# power.net
KiCad netlist of a schematic drawn in Altium Designer
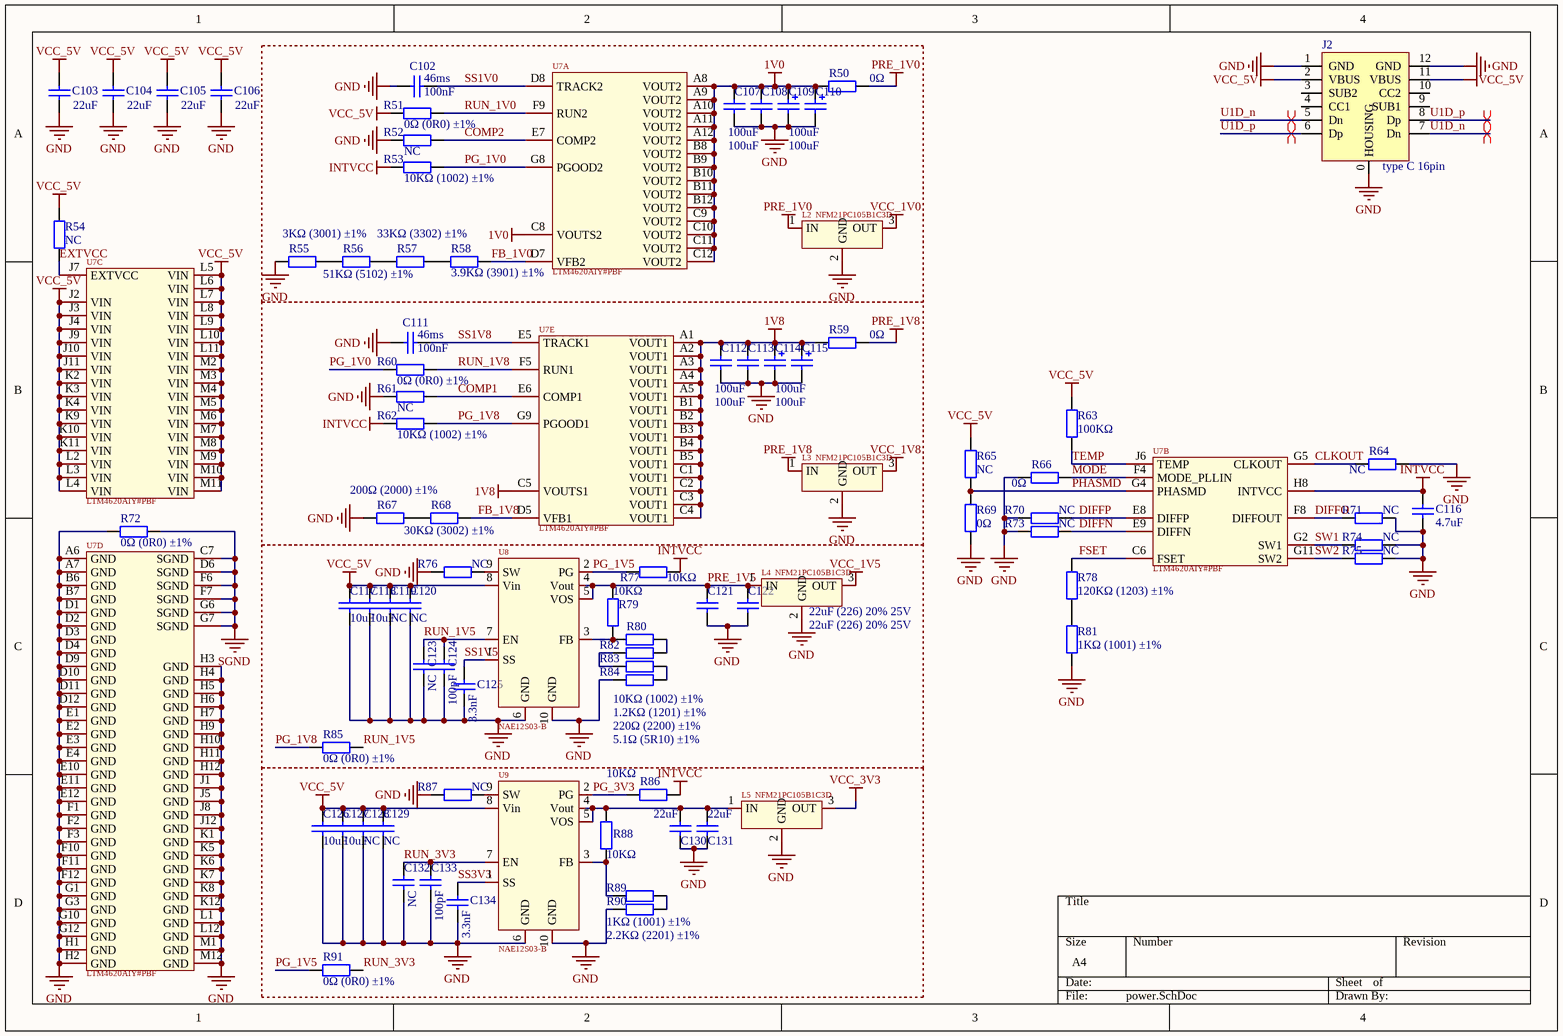
[diagram p0: power.SchDoc]

(export (version "E")
  (design (tool "Eeschema 10.0.6"))
  (components
    (comp (ref "C102")
      (value "100nF")
      (footprint "0805_C")
      (description "贴片电容")
      (libsource (lib "Miscellaneous Devices LC") (part "0805 100nF(104) 10% 50V"))
    )
    (comp (ref "C103")
      (value "22uF")
      (footprint "0805_C")
      (description "贴片电容")
      (libsource (lib "Miscellaneous Devices LC") (part "0805 22uF (226) 20% 25V"))
    )
    (comp (ref "C104")
      (value "22uF")
      (footprint "0805_C")
      (description "贴片电容")
      (libsource (lib "Miscellaneous Devices LC") (part "0805 22uF (226) 20% 25V"))
    )
    (comp (ref "C105")
      (value "22uF")
      (footprint "0805_C")
      (description "贴片电容")
      (libsource (lib "Miscellaneous Devices LC") (part "0805 22uF (226) 20% 25V"))
    )
    (comp (ref "C106")
      (value "22uF")
      (footprint "0805_C")
      (description "贴片电容")
      (libsource (lib "Miscellaneous Devices LC") (part "0805 22uF (226) 20% 25V"))
    )
    (comp (ref "C107")
      (value "100uF")
      (footprint "1206_C")
      (description "贴片电容")
      (libsource (lib "Miscellaneous Devices LC") (part "1206 100nF (104) 10% 50V"))
    )
    (comp (ref "C108")
      (value "100uF")
      (footprint "1206_C")
      (description "贴片电容")
      (libsource (lib "Miscellaneous Devices LC") (part "1206 100nF (104) 10% 50V"))
    )
    (comp (ref "C109")
      (value "100uF")
      (footprint "CASE-B_3528")
      (description "钽电容")
      (libsource (lib "Miscellaneous Devices LC") (part "3528 100uF (107) 10% 6.3V"))
    )
    (comp (ref "C110")
      (value "100uF")
      (footprint "CASE-B_3528")
      (description "钽电容")
      (libsource (lib "Miscellaneous Devices LC") (part "3528 100uF (107) 10% 6.3V"))
    )
    (comp (ref "C111")
      (value "100nF")
      (footprint "0805_C")
      (description "贴片电容")
      (libsource (lib "Miscellaneous Devices LC") (part "0805 100nF(104) 10% 50V"))
    )
    (comp (ref "C112")
      (value "100uF")
      (footprint "1206_C")
      (description "贴片电容")
      (libsource (lib "Miscellaneous Devices LC") (part "1206 100nF (104) 10% 50V"))
    )
    (comp (ref "C113")
      (value "100uF")
      (footprint "1206_C")
      (description "贴片电容")
      (libsource (lib "Miscellaneous Devices LC") (part "1206 100nF (104) 10% 50V"))
    )
    (comp (ref "C114")
      (value "100uF")
      (footprint "CASE-B_3528")
      (description "钽电容")
      (libsource (lib "Miscellaneous Devices LC") (part "3528 100uF (107) 10% 6.3V"))
    )
    (comp (ref "C115")
      (value "100uF")
      (footprint "CASE-B_3528")
      (description "钽电容")
      (libsource (lib "Miscellaneous Devices LC") (part "3528 100uF (107) 10% 6.3V"))
    )
    (comp (ref "C116")
      (value "4.7uF")
      (footprint "0805_C")
      (description "贴片电容")
      (libsource (lib "Miscellaneous Devices LC") (part "0805 4.7uF (475) 10% 25V"))
    )
    (comp (ref "C117")
      (value "10uF")
      (footprint "0805_C")
      (description "贴片电容")
      (libsource (lib "Miscellaneous Devices LC") (part "0805 10uF (106) 10% 25V"))
    )
    (comp (ref "C118")
      (value "10uF")
      (footprint "0805_C")
      (description "贴片电容")
      (libsource (lib "Miscellaneous Devices LC") (part "0805 10uF (106) 10% 25V"))
    )
    (comp (ref "C119")
      (value "NC")
      (footprint "0805_C")
      (description "贴片电容")
      (libsource (lib "Miscellaneous Devices LC") (part "0805 10uF (106) 10% 25V"))
    )
    (comp (ref "C120")
      (value "NC")
      (footprint "0805_C")
      (description "贴片电容")
      (libsource (lib "Miscellaneous Devices LC") (part "0805 10uF (106) 10% 25V"))
    )
    (comp (ref "C121")
      (value "22uF (226) 20% 25V")
      (footprint "0805_C")
      (description "贴片电容")
      (libsource (lib "Miscellaneous Devices LC") (part "0805 22uF (226) 20% 25V"))
    )
    (comp (ref "C122")
      (value "22uF (226) 20% 25V")
      (footprint "0805_C")
      (description "贴片电容")
      (libsource (lib "Miscellaneous Devices LC") (part "0805 22uF (226) 20% 25V"))
    )
    (comp (ref "C123")
      (value "NC")
      (footprint "0805_C")
      (description "贴片电容")
      (libsource (lib "Miscellaneous Devices LC") (part "0805 100pF (101) 5% 50V"))
    )
    (comp (ref "C124")
      (value "100pF")
      (footprint "0805_C")
      (description "贴片电容")
      (libsource (lib "Miscellaneous Devices LC") (part "0805 100pF (101) 5% 50V"))
    )
    (comp (ref "C125")
      (value "3.3nF")
      (footprint "0805_C")
      (description "贴片电容")
      (libsource (lib "Miscellaneous Devices LC") (part "0805 3.3nF (332) 10% 50V"))
    )
    (comp (ref "C126")
      (value "10uF")
      (footprint "0805_C")
      (description "贴片电容")
      (libsource (lib "Miscellaneous Devices LC") (part "0805 10uF (106) 10% 25V"))
    )
    (comp (ref "C127")
      (value "10uF")
      (footprint "0805_C")
      (description "贴片电容")
      (libsource (lib "Miscellaneous Devices LC") (part "0805 10uF (106) 10% 25V"))
    )
    (comp (ref "C128")
      (value "NC")
      (footprint "0805_C")
      (description "贴片电容")
      (libsource (lib "Miscellaneous Devices LC") (part "0805 10uF (106) 10% 25V"))
    )
    (comp (ref "C129")
      (value "NC")
      (footprint "0805_C")
      (description "贴片电容")
      (libsource (lib "Miscellaneous Devices LC") (part "0805 10uF (106) 10% 25V"))
    )
    (comp (ref "C130")
      (value "22uF")
      (footprint "0805_C")
      (description "贴片电容")
      (libsource (lib "Miscellaneous Devices LC") (part "0805 22uF (226) 20% 25V"))
    )
    (comp (ref "C131")
      (value "22uF")
      (footprint "0805_C")
      (description "贴片电容")
      (libsource (lib "Miscellaneous Devices LC") (part "0805 22uF (226) 20% 25V"))
    )
    (comp (ref "C132")
      (value "NC")
      (footprint "0805_C")
      (description "贴片电容")
      (libsource (lib "Miscellaneous Devices LC") (part "0805 100pF (101) 5% 50V"))
    )
    (comp (ref "C133")
      (value "100pF")
      (footprint "0805_C")
      (description "贴片电容")
      (libsource (lib "Miscellaneous Devices LC") (part "0805 100pF (101) 5% 50V"))
    )
    (comp (ref "C134")
      (value "3.3nF")
      (footprint "0805_C")
      (description "贴片电容")
      (libsource (lib "Miscellaneous Devices LC") (part "0805 3.3nF (332) 10% 50V"))
    )
    (comp (ref "J2")
      (value "type C 16pin")
      (footprint "USB type C  16pin")
      (description "16针脚C口")
      (libsource (lib "五向开关") (part "USB type C 16pin"))
    )
    (comp (ref "L2")
      (value "NFM21PC105B1C3D")
      (footprint "FILTER-SMD_3P-L2.0-W1.2-L")
      (description "穿心电容")
      (fields (field (name "MANUFACTURER") "muRata(村田)"))
      (libsource (lib "五向开关") (part "NFM21PC105B1C3D"))
    )
    (comp (ref "L3")
      (value "NFM21PC105B1C3D")
      (footprint "FILTER-SMD_3P-L2.0-W1.2-L")
      (description "穿心电容")
      (fields (field (name "MANUFACTURER") "muRata(村田)"))
      (libsource (lib "五向开关") (part "NFM21PC105B1C3D"))
    )
    (comp (ref "L4")
      (value "NFM21PC105B1C3D")
      (footprint "FILTER-SMD_3P-L2.0-W1.2-L")
      (description "穿心电容")
      (fields (field (name "MANUFACTURER") "muRata(村田)"))
      (libsource (lib "五向开关") (part "NFM21PC105B1C3D"))
    )
    (comp (ref "L5")
      (value "NFM21PC105B1C3D")
      (footprint "FILTER-SMD_3P-L2.0-W1.2-L")
      (description "穿心电容")
      (fields (field (name "MANUFACTURER") "muRata(村田)"))
      (libsource (lib "五向开关") (part "NFM21PC105B1C3D"))
    )
    (comp (ref "R50")
      (value "0Ω")
      (footprint "0805_R")
      (description "贴片电阻")
      (libsource (lib "") (part "0805 0Ω (0R0) 1%_1"))
    )
    (comp (ref "R51")
      (value "0Ω (0R0) ±1%")
      (footprint "0805_R")
      (description "贴片电阻")
      (libsource (lib "Miscellaneous Devices LC") (part "0805 0Ω (0R0) 1%"))
    )
    (comp (ref "R52")
      (value "NC")
      (footprint "0805_R")
      (description "贴片电阻")
      (libsource (lib "Miscellaneous Devices LC") (part "0805 33KΩ (3302) 1%"))
    )
    (comp (ref "R53")
      (value "10KΩ (1002) ±1%")
      (footprint "0805_R")
      (description "贴片电阻")
      (libsource (lib "Miscellaneous Devices LC") (part "0805 10KΩ (1002) 1%"))
    )
    (comp (ref "R54")
      (value "NC")
      (footprint "0805_R")
      (description "贴片电阻")
      (libsource (lib "Miscellaneous Devices LC") (part "0805 3KΩ (3001) 1%"))
    )
    (comp (ref "R55")
      (value "3KΩ (3001) ±1%")
      (footprint "0805_R")
      (description "贴片电阻")
      (libsource (lib "") (part "0805 3KΩ (3001) 1%_1"))
    )
    (comp (ref "R56")
      (value "51KΩ (5102) ±1%")
      (footprint "0805_R")
      (description "贴片电阻")
      (libsource (lib "Miscellaneous Devices LC") (part "0805 51KΩ (5102) 1%"))
    )
    (comp (ref "R57")
      (value "33KΩ (3302) ±1%")
      (footprint "0805_R")
      (description "贴片电阻")
      (libsource (lib "Miscellaneous Devices LC") (part "0805 33KΩ (3302) 1%"))
    )
    (comp (ref "R58")
      (value "3.9KΩ (3901) ±1%")
      (footprint "0805_R")
      (description "贴片电阻")
      (libsource (lib "Miscellaneous Devices LC") (part "0805 3.9KΩ (3901) 1%"))
    )
    (comp (ref "R59")
      (value "0Ω")
      (footprint "0805_R")
      (description "贴片电阻")
      (libsource (lib "") (part "0805 0Ω (0R0) 1%_1"))
    )
    (comp (ref "R60")
      (value "0Ω (0R0) ±1%")
      (footprint "0805_R")
      (description "贴片电阻")
      (libsource (lib "Miscellaneous Devices LC") (part "0805 0Ω (0R0) 1%"))
    )
    (comp (ref "R61")
      (value "NC")
      (footprint "0805_R")
      (description "贴片电阻")
      (libsource (lib "Miscellaneous Devices LC") (part "0805 33KΩ (3302) 1%"))
    )
    (comp (ref "R62")
      (value "10KΩ (1002) ±1%")
      (footprint "0805_R")
      (description "贴片电阻")
      (libsource (lib "Miscellaneous Devices LC") (part "0805 10KΩ (1002) 1%"))
    )
    (comp (ref "R63")
      (value "100KΩ")
      (footprint "0805_R")
      (description "贴片电阻")
      (libsource (lib "Miscellaneous Devices LC") (part "0805 100KΩ (1003) 1%"))
    )
    (comp (ref "R64")
      (value "NC")
      (footprint "0805_R")
      (description "贴片电阻")
      (libsource (lib "Miscellaneous Devices LC") (part "0805 0Ω (0R0) 1%"))
    )
    (comp (ref "R65")
      (value "NC")
      (footprint "0805_R")
      (description "贴片电阻")
      (libsource (lib "") (part "0805 0Ω (0R0) 1%_2"))
    )
    (comp (ref "R66")
      (value "0Ω")
      (footprint "0805_R")
      (description "贴片电阻")
      (libsource (lib "Miscellaneous Devices LC") (part "0805 0Ω (0R0) 1%"))
    )
    (comp (ref "R67")
      (value "200Ω (2000) ±1%")
      (footprint "0805_R")
      (description "贴片电阻")
      (libsource (lib "Miscellaneous Devices LC") (part "0805 200Ω (2000) 1%"))
    )
    (comp (ref "R68")
      (value "30KΩ (3002) ±1%")
      (footprint "0805_R")
      (description "贴片电阻")
      (libsource (lib "Miscellaneous Devices LC") (part "0805 33KΩ (3302) 1%"))
    )
    (comp (ref "R69")
      (value "0Ω")
      (footprint "0805_R")
      (description "贴片电阻")
      (libsource (lib "") (part "0805 0Ω (0R0) 1%_2"))
    )
    (comp (ref "R70")
      (value "NC")
      (footprint "0805_R")
      (description "贴片电阻")
      (libsource (lib "Miscellaneous Devices LC") (part "0805 0Ω (0R0) 1%"))
    )
    (comp (ref "R71")
      (value "NC")
      (footprint "0805_R")
      (description "贴片电阻")
      (libsource (lib "Miscellaneous Devices LC") (part "0805 0Ω (0R0) 1%"))
    )
    (comp (ref "R72")
      (value "0Ω (0R0) ±1%")
      (footprint "0402_R")
      (description "贴片电阻")
      (libsource (lib "Miscellaneous Devices LC") (part "0805 0Ω (0R0) 1%"))
    )
    (comp (ref "R73")
      (value "NC")
      (footprint "0805_R")
      (description "贴片电阻")
      (libsource (lib "Miscellaneous Devices LC") (part "0805 0Ω (0R0) 1%"))
    )
    (comp (ref "R74")
      (value "NC")
      (footprint "0805_R")
      (description "贴片电阻")
      (libsource (lib "Miscellaneous Devices LC") (part "0805 0Ω (0R0) 1%"))
    )
    (comp (ref "R75")
      (value "NC")
      (footprint "0805_R")
      (description "贴片电阻")
      (libsource (lib "Miscellaneous Devices LC") (part "0805 0Ω (0R0) 1%"))
    )
    (comp (ref "R76")
      (value "NC")
      (footprint "0805_R")
      (description "贴片电阻")
      (libsource (lib "Miscellaneous Devices LC") (part "0805 0Ω (0R0) 1%"))
    )
    (comp (ref "R77")
      (value "10KΩ")
      (footprint "0805_R")
      (description "贴片电阻")
      (libsource (lib "") (part "0805 10KΩ (1002) 1%_1"))
    )
    (comp (ref "R78")
      (value "120KΩ (1203) ±1%")
      (footprint "0805_R")
      (description "贴片电阻")
      (libsource (lib "Miscellaneous Devices LC") (part "0402 120KΩ (1203) 1%"))
    )
    (comp (ref "R79")
      (value "10KΩ")
      (footprint "0805_R")
      (description "贴片电阻")
      (libsource (lib "") (part "0805 10KΩ (1002) 1%_2"))
    )
    (comp (ref "R80")
      (value "10KΩ (1002) ±1%")
      (footprint "0805_R")
      (description "贴片电阻")
      (libsource (lib "") (part "0805 10KΩ (1002) 1%_1"))
    )
    (comp (ref "R81")
      (value "1KΩ (1001) ±1%")
      (footprint "0805_R")
      (description "贴片电阻")
      (libsource (lib "Miscellaneous Devices LC") (part "0402 1KΩ (1001) 1%"))
    )
    (comp (ref "R82")
      (value "1.2KΩ (1201) ±1%")
      (footprint "0805_R")
      (description "贴片电阻")
      (libsource (lib "Miscellaneous Devices LC") (part "0805 1.2KΩ (1201) 1%"))
    )
    (comp (ref "R83")
      (value "220Ω (2200) ±1%")
      (footprint "0805_R")
      (description "贴片电阻")
      (libsource (lib "Miscellaneous Devices LC") (part "0805 220Ω (2200) 1%"))
    )
    (comp (ref "R84")
      (value "5.1Ω (5R10) ±1%")
      (footprint "0805_R")
      (description "贴片电阻")
      (libsource (lib "Miscellaneous Devices LC") (part "0805 5.1Ω (5R10) 1%"))
    )
    (comp (ref "R85")
      (value "0Ω (0R0) ±1%")
      (footprint "0805_R")
      (description "贴片电阻")
      (libsource (lib "Miscellaneous Devices LC") (part "0805 0Ω (0R0) 1%"))
    )
    (comp (ref "R86")
      (value "10KΩ")
      (footprint "0805_R")
      (description "贴片电阻")
      (libsource (lib "") (part "0805 10KΩ (1002) 1%_1"))
    )
    (comp (ref "R87")
      (value "NC")
      (footprint "0805_R")
      (description "贴片电阻")
      (libsource (lib "Miscellaneous Devices LC") (part "0805 0Ω (0R0) 1%"))
    )
    (comp (ref "R88")
      (value "10KΩ")
      (footprint "0805_R")
      (description "贴片电阻")
      (libsource (lib "") (part "0805 10KΩ (1002) 1%_2"))
    )
    (comp (ref "R89")
      (value "2.2KΩ (2201) ±1%")
      (footprint "0805_R")
      (description "贴片电阻")
      (libsource (lib "Miscellaneous Devices LC") (part "0805 2.2KΩ (2201) 1%"))
    )
    (comp (ref "R90")
      (value "1KΩ (1001) ±1%")
      (footprint "0805_R")
      (description "贴片电阻")
      (libsource (lib "Miscellaneous Devices LC") (part "0805 1KΩ (1001) 1%"))
    )
    (comp (ref "R91")
      (value "0Ω (0R0) ±1%")
      (footprint "0805_R")
      (description "贴片电阻")
      (libsource (lib "Miscellaneous Devices LC") (part "0805 0Ω (0R0) 1%"))
    )
    (comp (ref "U7")
      (value "LTM4620AIY#PBF")
      (footprint "BGA-144_L15.0-W15.0-R12-C12-P1.27-BL")
      (description "ADI电源")
      (fields (field (name "MANUFACTURER") "ADI(亚德诺)"))
      (libsource (lib "五向开关") (part "LTM4620AIY#PBF"))
    )
    (comp (ref "U8")
      (value "NAE12S03-B")
      (footprint "PWRM-SMD_HUAWEI_NAE12S03")
      (description "华为电源模块")
      (fields (field (name "MANUFACTURER") "HUAWEI(华为)"))
      (libsource (lib "五向开关") (part "NAE12S03-B"))
    )
    (comp (ref "U9")
      (value "NAE12S03-B")
      (footprint "PWRM-SMD_HUAWEI_NAE12S03")
      (description "华为电源模块")
      (fields (field (name "MANUFACTURER") "HUAWEI(华为)"))
      (libsource (lib "五向开关") (part "NAE12S03-B"))
    )
  )
  (nets
    (net (code "1") (name "/CLKOUT") (class "Default")
      (node (ref "R64") (pin "2") (pinfunction "2_2") (pintype "passive"))
      (node (ref "U7") (pin "G5") (pinfunction "CLKOUT_G5") (pintype "passive"))
    )
    (net (code "2") (name "/COMP1") (class "Default")
      (node (ref "R61") (pin "2") (pinfunction "2_2") (pintype "passive"))
      (node (ref "U7") (pin "E6") (pinfunction "COMP1_E6") (pintype "passive"))
    )
    (net (code "3") (name "/COMP2") (class "Default")
      (node (ref "R52") (pin "2") (pinfunction "2_2") (pintype "passive"))
      (node (ref "U7") (pin "E7") (pinfunction "COMP2_E7") (pintype "passive"))
    )
    (net (code "4") (name "/DIFFN") (class "Default")
      (node (ref "R73") (pin "1") (pinfunction "1_1") (pintype "passive"))
      (node (ref "U7") (pin "E9") (pinfunction "DIFFN_E9") (pintype "passive"))
    )
    (net (code "5") (name "/DIFFO") (class "Default")
      (node (ref "R71") (pin "2") (pinfunction "2_2") (pintype "passive"))
      (node (ref "U7") (pin "F8") (pinfunction "DIFFOUT_F8") (pintype "passive"))
    )
    (net (code "6") (name "/DIFFP") (class "Default")
      (node (ref "R70") (pin "1") (pinfunction "1_1") (pintype "passive"))
      (node (ref "U7") (pin "E8") (pinfunction "DIFFP_E8") (pintype "passive"))
    )
    (net (code "7") (name "/EXTVCC") (class "Default")
      (node (ref "R54") (pin "2") (pinfunction "2_2") (pintype "passive"))
      (node (ref "U7") (pin "J7") (pinfunction "EXTVCC_J7") (pintype "passive"))
    )
    (net (code "8") (name "/FB_1V0") (class "Default")
      (node (ref "R58") (pin "2") (pinfunction "2_2") (pintype "passive"))
      (node (ref "U7") (pin "D7") (pinfunction "VFB2_D7") (pintype "passive"))
    )
    (net (code "9") (name "/FB_1V8") (class "Default")
      (node (ref "R68") (pin "2") (pinfunction "2_2") (pintype "passive"))
      (node (ref "U7") (pin "D5") (pinfunction "VFB1_D5") (pintype "passive"))
    )
    (net (code "10") (name "/FSET") (class "Default")
      (node (ref "R78") (pin "2") (pinfunction "2_2") (pintype "passive"))
      (node (ref "U7") (pin "C6") (pinfunction "FSET_C6") (pintype "passive"))
    )
    (net (code "11") (name "/MODE") (class "Default")
      (node (ref "R66") (pin "1") (pinfunction "1_1") (pintype "passive"))
      (node (ref "U7") (pin "F4") (pinfunction "MODE_PLLIN_F4") (pintype "passive"))
    )
    (net (code "12") (name "/PG_1V0") (class "Default")
      (node (ref "R53") (pin "1") (pinfunction "1_1") (pintype "passive"))
      (node (ref "R60") (pin "2") (pinfunction "2_2") (pintype "passive"))
      (node (ref "U7") (pin "G8") (pinfunction "PGOOD2_G8") (pintype "passive"))
    )
    (net (code "13") (name "/PG_1V5") (class "Default")
      (node (ref "R77") (pin "1") (pinfunction "1_1") (pintype "passive"))
      (node (ref "R91") (pin "2") (pinfunction "2_2") (pintype "passive"))
      (node (ref "U8") (pin "2") (pinfunction "PG_2") (pintype "passive"))
    )
    (net (code "14") (name "/PG_1V8") (class "Default")
      (node (ref "R62") (pin "1") (pinfunction "1_1") (pintype "passive"))
      (node (ref "R85") (pin "2") (pinfunction "2_2") (pintype "passive"))
      (node (ref "U7") (pin "G9") (pinfunction "PGOOD1_G9") (pintype "passive"))
    )
    (net (code "15") (name "/PG_3V3") (class "Default")
      (node (ref "R86") (pin "1") (pinfunction "1_1") (pintype "passive"))
      (node (ref "U9") (pin "2") (pinfunction "PG_2") (pintype "passive"))
    )
    (net (code "16") (name "/PHASMD") (class "Default")
      (node (ref "R65") (pin "1") (pinfunction "1_1") (pintype "passive"))
      (node (ref "R69") (pin "2") (pinfunction "2_2") (pintype "passive"))
      (node (ref "U7") (pin "G4") (pinfunction "PHASMD_G4") (pintype "passive"))
    )
    (net (code "17") (name "/PRE_1V5") (class "Default")
      (node (ref "C121") (pin "2") (pinfunction "2_2") (pintype "passive"))
      (node (ref "C122") (pin "2") (pinfunction "2_2") (pintype "passive"))
      (node (ref "L4") (pin "1") (pinfunction "IN_1") (pintype "passive"))
      (node (ref "R79") (pin "2") (pinfunction "2_2") (pintype "passive"))
      (node (ref "U8") (pin "4") (pinfunction "Vout_4") (pintype "passive"))
      (node (ref "U8") (pin "5") (pinfunction "VOS_5") (pintype "passive"))
    )
    (net (code "18") (name "/RUN_1V0") (class "Default")
      (node (ref "R51") (pin "1") (pinfunction "1_1") (pintype "passive"))
      (node (ref "U7") (pin "F9") (pinfunction "RUN2_F9") (pintype "passive"))
    )
    (net (code "19") (name "/RUN_1V5") (class "Default")
      (node (ref "C123") (pin "2") (pinfunction "2_2") (pintype "passive"))
      (node (ref "C124") (pin "2") (pinfunction "2_2") (pintype "passive"))
      (node (ref "R85") (pin "1") (pinfunction "1_1") (pintype "passive"))
      (node (ref "U8") (pin "7") (pinfunction "EN_7") (pintype "passive"))
    )
    (net (code "20") (name "/RUN_1V8") (class "Default")
      (node (ref "R60") (pin "1") (pinfunction "1_1") (pintype "passive"))
      (node (ref "U7") (pin "F5") (pinfunction "RUN1_F5") (pintype "passive"))
    )
    (net (code "21") (name "/RUN_3V3") (class "Default")
      (node (ref "C132") (pin "2") (pinfunction "2_2") (pintype "passive"))
      (node (ref "C133") (pin "2") (pinfunction "2_2") (pintype "passive"))
      (node (ref "R91") (pin "1") (pinfunction "1_1") (pintype "passive"))
      (node (ref "U9") (pin "7") (pinfunction "EN_7") (pintype "passive"))
    )
    (net (code "22") (name "/SS1V0") (class "Default")
      (node (ref "C102") (pin "1") (pinfunction "1_1") (pintype "passive"))
      (node (ref "U7") (pin "D8") (pinfunction "TRACK2_D8") (pintype "passive"))
    )
    (net (code "23") (name "/SS1V5") (class "Default")
      (node (ref "C125") (pin "2") (pinfunction "2_2") (pintype "passive"))
      (node (ref "U8") (pin "1") (pinfunction "SS_1") (pintype "passive"))
    )
    (net (code "24") (name "/SS1V8") (class "Default")
      (node (ref "C111") (pin "1") (pinfunction "1_1") (pintype "passive"))
      (node (ref "U7") (pin "E5") (pinfunction "TRACK1_E5") (pintype "passive"))
    )
    (net (code "25") (name "/SS3V3") (class "Default")
      (node (ref "C134") (pin "2") (pinfunction "2_2") (pintype "passive"))
      (node (ref "U9") (pin "1") (pinfunction "SS_1") (pintype "passive"))
    )
    (net (code "26") (name "/SW1") (class "Default")
      (node (ref "R74") (pin "2") (pinfunction "2_2") (pintype "passive"))
      (node (ref "U7") (pin "G2") (pinfunction "SW1_G2") (pintype "passive"))
    )
    (net (code "27") (name "/SW2") (class "Default")
      (node (ref "R75") (pin "2") (pinfunction "2_2") (pintype "passive"))
      (node (ref "U7") (pin "G11") (pinfunction "SW2_G11") (pintype "passive"))
    )
    (net (code "28") (name "/TEMP") (class "Default")
      (node (ref "R63") (pin "1") (pinfunction "1_1") (pintype "passive"))
      (node (ref "U7") (pin "J6") (pinfunction "TEMP_J6") (pintype "passive"))
    )
    (net (code "29") (name "/U1D_n") (class "Default")
      (node (ref "J2") (pin "5") (pinfunction "Dn_5") (pintype "passive"))
      (node (ref "J2") (pin "7") (pinfunction "Dn_7") (pintype "passive"))
    )
    (net (code "30") (name "/U1D_p") (class "Default")
      (node (ref "J2") (pin "6") (pinfunction "Dp_6") (pintype "passive"))
      (node (ref "J2") (pin "8") (pinfunction "Dp_8") (pintype "passive"))
    )
    (net (code "31") (name "1V0") (class "Default")
      (node (ref "C107") (pin "2") (pinfunction "2_2") (pintype "passive"))
      (node (ref "C108") (pin "2") (pinfunction "2_2") (pintype "passive"))
      (node (ref "C109") (pin "1") (pinfunction "1_1") (pintype "passive"))
      (node (ref "C110") (pin "1") (pinfunction "1_1") (pintype "passive"))
      (node (ref "R50") (pin "1") (pinfunction "1_1") (pintype "passive"))
      (node (ref "U7") (pin "A10") (pinfunction "VOUT2_A10") (pintype "passive"))
      (node (ref "U7") (pin "A11") (pinfunction "VOUT2_A11") (pintype "passive"))
      (node (ref "U7") (pin "A12") (pinfunction "VOUT2_A12") (pintype "passive"))
      (node (ref "U7") (pin "A8") (pinfunction "VOUT2_A8") (pintype "passive"))
      (node (ref "U7") (pin "A9") (pinfunction "VOUT2_A9") (pintype "passive"))
      (node (ref "U7") (pin "B10") (pinfunction "VOUT2_B10") (pintype "passive"))
      (node (ref "U7") (pin "B11") (pinfunction "VOUT2_B11") (pintype "passive"))
      (node (ref "U7") (pin "B12") (pinfunction "VOUT2_B12") (pintype "passive"))
      (node (ref "U7") (pin "B8") (pinfunction "VOUT2_B8") (pintype "passive"))
      (node (ref "U7") (pin "B9") (pinfunction "VOUT2_B9") (pintype "passive"))
      (node (ref "U7") (pin "C10") (pinfunction "VOUT2_C10") (pintype "passive"))
      (node (ref "U7") (pin "C11") (pinfunction "VOUT2_C11") (pintype "passive"))
      (node (ref "U7") (pin "C12") (pinfunction "VOUT2_C12") (pintype "passive"))
      (node (ref "U7") (pin "C8") (pinfunction "VOUTS2_C8") (pintype "passive"))
      (node (ref "U7") (pin "C9") (pinfunction "VOUT2_C9") (pintype "passive"))
    )
    (net (code "32") (name "1V8") (class "Default")
      (node (ref "C112") (pin "2") (pinfunction "2_2") (pintype "passive"))
      (node (ref "C113") (pin "2") (pinfunction "2_2") (pintype "passive"))
      (node (ref "C114") (pin "1") (pinfunction "1_1") (pintype "passive"))
      (node (ref "C115") (pin "1") (pinfunction "1_1") (pintype "passive"))
      (node (ref "R59") (pin "1") (pinfunction "1_1") (pintype "passive"))
      (node (ref "U7") (pin "A1") (pinfunction "VOUT1_A1") (pintype "passive"))
      (node (ref "U7") (pin "A2") (pinfunction "VOUT1_A2") (pintype "passive"))
      (node (ref "U7") (pin "A3") (pinfunction "VOUT1_A3") (pintype "passive"))
      (node (ref "U7") (pin "A4") (pinfunction "VOUT1_A4") (pintype "passive"))
      (node (ref "U7") (pin "A5") (pinfunction "VOUT1_A5") (pintype "passive"))
      (node (ref "U7") (pin "B1") (pinfunction "VOUT1_B1") (pintype "passive"))
      (node (ref "U7") (pin "B2") (pinfunction "VOUT1_B2") (pintype "passive"))
      (node (ref "U7") (pin "B3") (pinfunction "VOUT1_B3") (pintype "passive"))
      (node (ref "U7") (pin "B4") (pinfunction "VOUT1_B4") (pintype "passive"))
      (node (ref "U7") (pin "B5") (pinfunction "VOUT1_B5") (pintype "passive"))
      (node (ref "U7") (pin "C1") (pinfunction "VOUT1_C1") (pintype "passive"))
      (node (ref "U7") (pin "C2") (pinfunction "VOUT1_C2") (pintype "passive"))
      (node (ref "U7") (pin "C3") (pinfunction "VOUT1_C3") (pintype "passive"))
      (node (ref "U7") (pin "C4") (pinfunction "VOUT1_C4") (pintype "passive"))
      (node (ref "U7") (pin "C5") (pinfunction "VOUTS1_C5") (pintype "passive"))
    )
    (net (code "33") (name "GND") (class "Default")
      (node (ref "C102") (pin "2") (pinfunction "2_2") (pintype "passive"))
      (node (ref "C103") (pin "1") (pinfunction "1_1") (pintype "passive"))
      (node (ref "C104") (pin "1") (pinfunction "1_1") (pintype "passive"))
      (node (ref "C105") (pin "1") (pinfunction "1_1") (pintype "passive"))
      (node (ref "C106") (pin "1") (pinfunction "1_1") (pintype "passive"))
      (node (ref "C107") (pin "1") (pinfunction "1_1") (pintype "passive"))
      (node (ref "C108") (pin "1") (pinfunction "1_1") (pintype "passive"))
      (node (ref "C109") (pin "2") (pinfunction "2_2") (pintype "passive"))
      (node (ref "C110") (pin "2") (pinfunction "2_2") (pintype "passive"))
      (node (ref "C111") (pin "2") (pinfunction "2_2") (pintype "passive"))
      (node (ref "C112") (pin "1") (pinfunction "1_1") (pintype "passive"))
      (node (ref "C113") (pin "1") (pinfunction "1_1") (pintype "passive"))
      (node (ref "C114") (pin "2") (pinfunction "2_2") (pintype "passive"))
      (node (ref "C115") (pin "2") (pinfunction "2_2") (pintype "passive"))
      (node (ref "C116") (pin "1") (pinfunction "1_1") (pintype "passive"))
      (node (ref "C117") (pin "1") (pinfunction "1_1") (pintype "passive"))
      (node (ref "C118") (pin "1") (pinfunction "1_1") (pintype "passive"))
      (node (ref "C119") (pin "1") (pinfunction "1_1") (pintype "passive"))
      (node (ref "C120") (pin "1") (pinfunction "1_1") (pintype "passive"))
      (node (ref "C121") (pin "1") (pinfunction "1_1") (pintype "passive"))
      (node (ref "C122") (pin "1") (pinfunction "1_1") (pintype "passive"))
      (node (ref "C123") (pin "1") (pinfunction "1_1") (pintype "passive"))
      (node (ref "C124") (pin "1") (pinfunction "1_1") (pintype "passive"))
      (node (ref "C125") (pin "1") (pinfunction "1_1") (pintype "passive"))
      (node (ref "C126") (pin "1") (pinfunction "1_1") (pintype "passive"))
      (node (ref "C127") (pin "1") (pinfunction "1_1") (pintype "passive"))
      (node (ref "C128") (pin "1") (pinfunction "1_1") (pintype "passive"))
      (node (ref "C129") (pin "1") (pinfunction "1_1") (pintype "passive"))
      (node (ref "C130") (pin "1") (pinfunction "1_1") (pintype "passive"))
      (node (ref "C131") (pin "1") (pinfunction "1_1") (pintype "passive"))
      (node (ref "C132") (pin "1") (pinfunction "1_1") (pintype "passive"))
      (node (ref "C133") (pin "1") (pinfunction "1_1") (pintype "passive"))
      (node (ref "C134") (pin "1") (pinfunction "1_1") (pintype "passive"))
      (node (ref "J2") (pin "0") (pinfunction "HOUSING_0") (pintype "passive"))
      (node (ref "J2") (pin "1") (pinfunction "GND_1") (pintype "passive"))
      (node (ref "J2") (pin "12") (pinfunction "GND_12") (pintype "passive"))
      (node (ref "L2") (pin "2") (pinfunction "GND_2") (pintype "passive"))
      (node (ref "L3") (pin "2") (pinfunction "GND_2") (pintype "passive"))
      (node (ref "L4") (pin "2") (pinfunction "GND_2") (pintype "passive"))
      (node (ref "L5") (pin "2") (pinfunction "GND_2") (pintype "passive"))
      (node (ref "R52") (pin "1") (pinfunction "1_1") (pintype "passive"))
      (node (ref "R55") (pin "2") (pinfunction "2_2") (pintype "passive"))
      (node (ref "R61") (pin "1") (pinfunction "1_1") (pintype "passive"))
      (node (ref "R64") (pin "1") (pinfunction "1_1") (pintype "passive"))
      (node (ref "R66") (pin "2") (pinfunction "2_2") (pintype "passive"))
      (node (ref "R67") (pin "1") (pinfunction "1_1") (pintype "passive"))
      (node (ref "R69") (pin "1") (pinfunction "1_1") (pintype "passive"))
      (node (ref "R70") (pin "2") (pinfunction "2_2") (pintype "passive"))
      (node (ref "R71") (pin "1") (pinfunction "1_1") (pintype "passive"))
      (node (ref "R72") (pin "2") (pinfunction "2_2") (pintype "passive"))
      (node (ref "R73") (pin "2") (pinfunction "2_2") (pintype "passive"))
      (node (ref "R74") (pin "1") (pinfunction "1_1") (pintype "passive"))
      (node (ref "R75") (pin "1") (pinfunction "1_1") (pintype "passive"))
      (node (ref "R76") (pin "2") (pinfunction "2_2") (pintype "passive"))
      (node (ref "R81") (pin "1") (pinfunction "1_1") (pintype "passive"))
      (node (ref "R84") (pin "2") (pinfunction "2_2") (pintype "passive"))
      (node (ref "R87") (pin "2") (pinfunction "2_2") (pintype "passive"))
      (node (ref "R90") (pin "2") (pinfunction "2_2") (pintype "passive"))
      (node (ref "U7") (pin "A6") (pinfunction "GND_A6") (pintype "passive"))
      (node (ref "U7") (pin "A7") (pinfunction "GND_A7") (pintype "passive"))
      (node (ref "U7") (pin "B6") (pinfunction "GND_B6") (pintype "passive"))
      (node (ref "U7") (pin "B7") (pinfunction "GND_B7") (pintype "passive"))
      (node (ref "U7") (pin "D1") (pinfunction "GND_D1") (pintype "passive"))
      (node (ref "U7") (pin "D10") (pinfunction "GND_D10") (pintype "passive"))
      (node (ref "U7") (pin "D11") (pinfunction "GND_D11") (pintype "passive"))
      (node (ref "U7") (pin "D12") (pinfunction "GND_D12") (pintype "passive"))
      (node (ref "U7") (pin "D2") (pinfunction "GND_D2") (pintype "passive"))
      (node (ref "U7") (pin "D3") (pinfunction "GND_D3") (pintype "passive"))
      (node (ref "U7") (pin "D4") (pinfunction "GND_D4") (pintype "passive"))
      (node (ref "U7") (pin "D9") (pinfunction "GND_D9") (pintype "passive"))
      (node (ref "U7") (pin "E1") (pinfunction "GND_E1") (pintype "passive"))
      (node (ref "U7") (pin "E10") (pinfunction "GND_E10") (pintype "passive"))
      (node (ref "U7") (pin "E11") (pinfunction "GND_E11") (pintype "passive"))
      (node (ref "U7") (pin "E12") (pinfunction "GND_E12") (pintype "passive"))
      (node (ref "U7") (pin "E2") (pinfunction "GND_E2") (pintype "passive"))
      (node (ref "U7") (pin "E3") (pinfunction "GND_E3") (pintype "passive"))
      (node (ref "U7") (pin "E4") (pinfunction "GND_E4") (pintype "passive"))
      (node (ref "U7") (pin "F1") (pinfunction "GND_F1") (pintype "passive"))
      (node (ref "U7") (pin "F10") (pinfunction "GND_F10") (pintype "passive"))
      (node (ref "U7") (pin "F11") (pinfunction "GND_F11") (pintype "passive"))
      (node (ref "U7") (pin "F12") (pinfunction "GND_F12") (pintype "passive"))
      (node (ref "U7") (pin "F2") (pinfunction "GND_F2") (pintype "passive"))
      (node (ref "U7") (pin "F3") (pinfunction "GND_F3") (pintype "passive"))
      (node (ref "U7") (pin "G1") (pinfunction "GND_G1") (pintype "passive"))
      (node (ref "U7") (pin "G10") (pinfunction "GND_G10") (pintype "passive"))
      (node (ref "U7") (pin "G12") (pinfunction "GND_G12") (pintype "passive"))
      (node (ref "U7") (pin "G3") (pinfunction "GND_G3") (pintype "passive"))
      (node (ref "U7") (pin "H1") (pinfunction "GND_H1") (pintype "passive"))
      (node (ref "U7") (pin "H10") (pinfunction "GND_H10") (pintype "passive"))
      (node (ref "U7") (pin "H11") (pinfunction "GND_H11") (pintype "passive"))
      (node (ref "U7") (pin "H12") (pinfunction "GND_H12") (pintype "passive"))
      (node (ref "U7") (pin "H2") (pinfunction "GND_H2") (pintype "passive"))
      (node (ref "U7") (pin "H3") (pinfunction "GND_H3") (pintype "passive"))
      (node (ref "U7") (pin "H4") (pinfunction "GND_H4") (pintype "passive"))
      (node (ref "U7") (pin "H5") (pinfunction "GND_H5") (pintype "passive"))
      (node (ref "U7") (pin "H6") (pinfunction "GND_H6") (pintype "passive"))
      (node (ref "U7") (pin "H7") (pinfunction "GND_H7") (pintype "passive"))
      (node (ref "U7") (pin "H9") (pinfunction "GND_H9") (pintype "passive"))
      (node (ref "U7") (pin "J1") (pinfunction "GND_J1") (pintype "passive"))
      (node (ref "U7") (pin "J12") (pinfunction "GND_J12") (pintype "passive"))
      (node (ref "U7") (pin "J5") (pinfunction "GND_J5") (pintype "passive"))
      (node (ref "U7") (pin "J8") (pinfunction "GND_J8") (pintype "passive"))
      (node (ref "U7") (pin "K1") (pinfunction "GND_K1") (pintype "passive"))
      (node (ref "U7") (pin "K12") (pinfunction "GND_K12") (pintype "passive"))
      (node (ref "U7") (pin "K5") (pinfunction "GND_K5") (pintype "passive"))
      (node (ref "U7") (pin "K6") (pinfunction "GND_K6") (pintype "passive"))
      (node (ref "U7") (pin "K7") (pinfunction "GND_K7") (pintype "passive"))
      (node (ref "U7") (pin "K8") (pinfunction "GND_K8") (pintype "passive"))
      (node (ref "U7") (pin "L1") (pinfunction "GND_L1") (pintype "passive"))
      (node (ref "U7") (pin "L12") (pinfunction "GND_L12") (pintype "passive"))
      (node (ref "U7") (pin "M1") (pinfunction "GND_M1") (pintype "passive"))
      (node (ref "U7") (pin "M12") (pinfunction "GND_M12") (pintype "passive"))
      (node (ref "U8") (pin "10") (pinfunction "GND_10") (pintype "passive"))
      (node (ref "U8") (pin "6") (pinfunction "GND_6") (pintype "passive"))
      (node (ref "U9") (pin "10") (pinfunction "GND_10") (pintype "passive"))
      (node (ref "U9") (pin "6") (pinfunction "GND_6") (pintype "passive"))
    )
    (net (code "34") (name "INTVCC") (class "Default")
      (node (ref "C116") (pin "2") (pinfunction "2_2") (pintype "passive"))
      (node (ref "R53") (pin "2") (pinfunction "2_2") (pintype "passive"))
      (node (ref "R62") (pin "2") (pinfunction "2_2") (pintype "passive"))
      (node (ref "R77") (pin "2") (pinfunction "2_2") (pintype "passive"))
      (node (ref "R86") (pin "2") (pinfunction "2_2") (pintype "passive"))
      (node (ref "U7") (pin "H8") (pinfunction "INTVCC_H8") (pintype "passive"))
    )
    (net (code "35") (name "Net-(L5-IN)") (class "Default")
      (node (ref "C130") (pin "2") (pinfunction "2_2") (pintype "passive"))
      (node (ref "C131") (pin "2") (pinfunction "2_2") (pintype "passive"))
      (node (ref "L5") (pin "1") (pinfunction "IN_1") (pintype "passive"))
      (node (ref "R88") (pin "2") (pinfunction "2_2") (pintype "passive"))
      (node (ref "U9") (pin "4") (pinfunction "Vout_4") (pintype "passive"))
      (node (ref "U9") (pin "5") (pinfunction "VOS_5") (pintype "passive"))
    )
    (net (code "36") (name "Net-(R55-Pad1)") (class "Default")
      (node (ref "R55") (pin "1") (pinfunction "1_1") (pintype "passive"))
      (node (ref "R56") (pin "1") (pinfunction "1_1") (pintype "passive"))
    )
    (net (code "37") (name "Net-(R56-Pad2)") (class "Default")
      (node (ref "R56") (pin "2") (pinfunction "2_2") (pintype "passive"))
      (node (ref "R57") (pin "1") (pinfunction "1_1") (pintype "passive"))
    )
    (net (code "38") (name "Net-(R57-Pad2)") (class "Default")
      (node (ref "R57") (pin "2") (pinfunction "2_2") (pintype "passive"))
      (node (ref "R58") (pin "1") (pinfunction "1_1") (pintype "passive"))
    )
    (net (code "39") (name "Net-(R67-Pad2)") (class "Default")
      (node (ref "R67") (pin "2") (pinfunction "2_2") (pintype "passive"))
      (node (ref "R68") (pin "1") (pinfunction "1_1") (pintype "passive"))
    )
    (net (code "40") (name "Net-(R78-Pad1)") (class "Default")
      (node (ref "R78") (pin "1") (pinfunction "1_1") (pintype "passive"))
      (node (ref "R81") (pin "2") (pinfunction "2_2") (pintype "passive"))
    )
    (net (code "41") (name "Net-(R80-Pad2)") (class "Default")
      (node (ref "R80") (pin "2") (pinfunction "2_2") (pintype "passive"))
      (node (ref "R82") (pin "1") (pinfunction "1_1") (pintype "passive"))
    )
    (net (code "42") (name "Net-(R82-Pad2)") (class "Default")
      (node (ref "R82") (pin "2") (pinfunction "2_2") (pintype "passive"))
      (node (ref "R83") (pin "2") (pinfunction "2_2") (pintype "passive"))
    )
    (net (code "43") (name "Net-(R83-Pad1)") (class "Default")
      (node (ref "R83") (pin "1") (pinfunction "1_1") (pintype "passive"))
      (node (ref "R84") (pin "1") (pinfunction "1_1") (pintype "passive"))
    )
    (net (code "44") (name "Net-(R89-Pad2)") (class "Default")
      (node (ref "R89") (pin "2") (pinfunction "2_2") (pintype "passive"))
      (node (ref "R90") (pin "1") (pinfunction "1_1") (pintype "passive"))
    )
    (net (code "45") (name "Net-(U8-FB)") (class "Default")
      (node (ref "R79") (pin "1") (pinfunction "1_1") (pintype "passive"))
      (node (ref "R80") (pin "1") (pinfunction "1_1") (pintype "passive"))
      (node (ref "U8") (pin "3") (pinfunction "FB_3") (pintype "passive"))
    )
    (net (code "46") (name "Net-(U8-SW)") (class "Default")
      (node (ref "R76") (pin "1") (pinfunction "1_1") (pintype "passive"))
      (node (ref "U8") (pin "9") (pinfunction "SW_9") (pintype "passive"))
    )
    (net (code "47") (name "Net-(U9-FB)") (class "Default")
      (node (ref "R88") (pin "1") (pinfunction "1_1") (pintype "passive"))
      (node (ref "R89") (pin "1") (pinfunction "1_1") (pintype "passive"))
      (node (ref "U9") (pin "3") (pinfunction "FB_3") (pintype "passive"))
    )
    (net (code "48") (name "Net-(U9-SW)") (class "Default")
      (node (ref "R87") (pin "1") (pinfunction "1_1") (pintype "passive"))
      (node (ref "U9") (pin "9") (pinfunction "SW_9") (pintype "passive"))
    )
    (net (code "49") (name "PRE_1V0") (class "Default")
      (node (ref "L2") (pin "1") (pinfunction "IN_1") (pintype "passive"))
      (node (ref "R50") (pin "2") (pinfunction "2_2") (pintype "passive"))
    )
    (net (code "50") (name "PRE_1V8") (class "Default")
      (node (ref "L3") (pin "1") (pinfunction "IN_1") (pintype "passive"))
      (node (ref "R59") (pin "2") (pinfunction "2_2") (pintype "passive"))
    )
    (net (code "51") (name "SGND") (class "Default")
      (node (ref "R72") (pin "1") (pinfunction "1_1") (pintype "passive"))
      (node (ref "U7") (pin "C7") (pinfunction "SGND_C7") (pintype "passive"))
      (node (ref "U7") (pin "D6") (pinfunction "SGND_D6") (pintype "passive"))
      (node (ref "U7") (pin "F6") (pinfunction "SGND_F6") (pintype "passive"))
      (node (ref "U7") (pin "F7") (pinfunction "SGND_F7") (pintype "passive"))
      (node (ref "U7") (pin "G6") (pinfunction "SGND_G6") (pintype "passive"))
      (node (ref "U7") (pin "G7") (pinfunction "SGND_G7") (pintype "passive"))
    )
    (net (code "52") (name "VCC_1V0") (class "Default")
      (node (ref "L2") (pin "3") (pinfunction "OUT_3") (pintype "passive"))
    )
    (net (code "53") (name "VCC_1V5") (class "Default")
      (node (ref "L4") (pin "3") (pinfunction "OUT_3") (pintype "passive"))
    )
    (net (code "54") (name "VCC_1V8") (class "Default")
      (node (ref "L3") (pin "3") (pinfunction "OUT_3") (pintype "passive"))
    )
    (net (code "55") (name "VCC_3V3") (class "Default")
      (node (ref "L5") (pin "3") (pinfunction "OUT_3") (pintype "passive"))
    )
    (net (code "56") (name "VCC_5V") (class "Default")
      (node (ref "C103") (pin "2") (pinfunction "2_2") (pintype "passive"))
      (node (ref "C104") (pin "2") (pinfunction "2_2") (pintype "passive"))
      (node (ref "C105") (pin "2") (pinfunction "2_2") (pintype "passive"))
      (node (ref "C106") (pin "2") (pinfunction "2_2") (pintype "passive"))
      (node (ref "C117") (pin "2") (pinfunction "2_2") (pintype "passive"))
      (node (ref "C118") (pin "2") (pinfunction "2_2") (pintype "passive"))
      (node (ref "C119") (pin "2") (pinfunction "2_2") (pintype "passive"))
      (node (ref "C120") (pin "2") (pinfunction "2_2") (pintype "passive"))
      (node (ref "C126") (pin "2") (pinfunction "2_2") (pintype "passive"))
      (node (ref "C127") (pin "2") (pinfunction "2_2") (pintype "passive"))
      (node (ref "C128") (pin "2") (pinfunction "2_2") (pintype "passive"))
      (node (ref "C129") (pin "2") (pinfunction "2_2") (pintype "passive"))
      (node (ref "J2") (pin "11") (pinfunction "VBUS_11") (pintype "passive"))
      (node (ref "J2") (pin "2") (pinfunction "VBUS_2") (pintype "passive"))
      (node (ref "R51") (pin "2") (pinfunction "2_2") (pintype "passive"))
      (node (ref "R54") (pin "1") (pinfunction "1_1") (pintype "passive"))
      (node (ref "R63") (pin "2") (pinfunction "2_2") (pintype "passive"))
      (node (ref "R65") (pin "2") (pinfunction "2_2") (pintype "passive"))
      (node (ref "U7") (pin "J10") (pinfunction "VIN_J10") (pintype "passive"))
      (node (ref "U7") (pin "J11") (pinfunction "VIN_J11") (pintype "passive"))
      (node (ref "U7") (pin "J2") (pinfunction "VIN_J2") (pintype "passive"))
      (node (ref "U7") (pin "J3") (pinfunction "VIN_J3") (pintype "passive"))
      (node (ref "U7") (pin "J4") (pinfunction "VIN_J4") (pintype "passive"))
      (node (ref "U7") (pin "J9") (pinfunction "VIN_J9") (pintype "passive"))
      (node (ref "U7") (pin "K10") (pinfunction "VIN_K10") (pintype "passive"))
      (node (ref "U7") (pin "K11") (pinfunction "VIN_K11") (pintype "passive"))
      (node (ref "U7") (pin "K2") (pinfunction "VIN_K2") (pintype "passive"))
      (node (ref "U7") (pin "K3") (pinfunction "VIN_K3") (pintype "passive"))
      (node (ref "U7") (pin "K4") (pinfunction "VIN_K4") (pintype "passive"))
      (node (ref "U7") (pin "K9") (pinfunction "VIN_K9") (pintype "passive"))
      (node (ref "U7") (pin "L10") (pinfunction "VIN_L10") (pintype "passive"))
      (node (ref "U7") (pin "L11") (pinfunction "VIN_L11") (pintype "passive"))
      (node (ref "U7") (pin "L2") (pinfunction "VIN_L2") (pintype "passive"))
      (node (ref "U7") (pin "L3") (pinfunction "VIN_L3") (pintype "passive"))
      (node (ref "U7") (pin "L4") (pinfunction "VIN_L4") (pintype "passive"))
      (node (ref "U7") (pin "L5") (pinfunction "VIN_L5") (pintype "passive"))
      (node (ref "U7") (pin "L6") (pinfunction "VIN_L6") (pintype "passive"))
      (node (ref "U7") (pin "L7") (pinfunction "VIN_L7") (pintype "passive"))
      (node (ref "U7") (pin "L8") (pinfunction "VIN_L8") (pintype "passive"))
      (node (ref "U7") (pin "L9") (pinfunction "VIN_L9") (pintype "passive"))
      (node (ref "U7") (pin "M10") (pinfunction "VIN_M10") (pintype "passive"))
      (node (ref "U7") (pin "M11") (pinfunction "VIN_M11") (pintype "passive"))
      (node (ref "U7") (pin "M2") (pinfunction "VIN_M2") (pintype "passive"))
      (node (ref "U7") (pin "M3") (pinfunction "VIN_M3") (pintype "passive"))
      (node (ref "U7") (pin "M4") (pinfunction "VIN_M4") (pintype "passive"))
      (node (ref "U7") (pin "M5") (pinfunction "VIN_M5") (pintype "passive"))
      (node (ref "U7") (pin "M6") (pinfunction "VIN_M6") (pintype "passive"))
      (node (ref "U7") (pin "M7") (pinfunction "VIN_M7") (pintype "passive"))
      (node (ref "U7") (pin "M8") (pinfunction "VIN_M8") (pintype "passive"))
      (node (ref "U7") (pin "M9") (pinfunction "VIN_M9") (pintype "passive"))
      (node (ref "U8") (pin "8") (pinfunction "Vin_8") (pintype "passive"))
      (node (ref "U9") (pin "8") (pinfunction "Vin_8") (pintype "passive"))
    )
    (net (code "57") (name "unconnected-(J2-CC1-Pad4)") (class "Default")
      (node (ref "J2") (pin "4") (pinfunction "CC1_4") (pintype "passive"))
    )
    (net (code "58") (name "unconnected-(J2-CC2-Pad10)") (class "Default")
      (node (ref "J2") (pin "10") (pinfunction "CC2_10") (pintype "passive"))
    )
    (net (code "59") (name "unconnected-(J2-SUB1-Pad9)") (class "Default")
      (node (ref "J2") (pin "9") (pinfunction "SUB1_9") (pintype "passive"))
    )
    (net (code "60") (name "unconnected-(J2-SUB2-Pad3)") (class "Default")
      (node (ref "J2") (pin "3") (pinfunction "SUB2_3") (pintype "passive"))
    )
  )
)
